# untitled.net
KiCad netlist of a schematic drawn in EAGLE
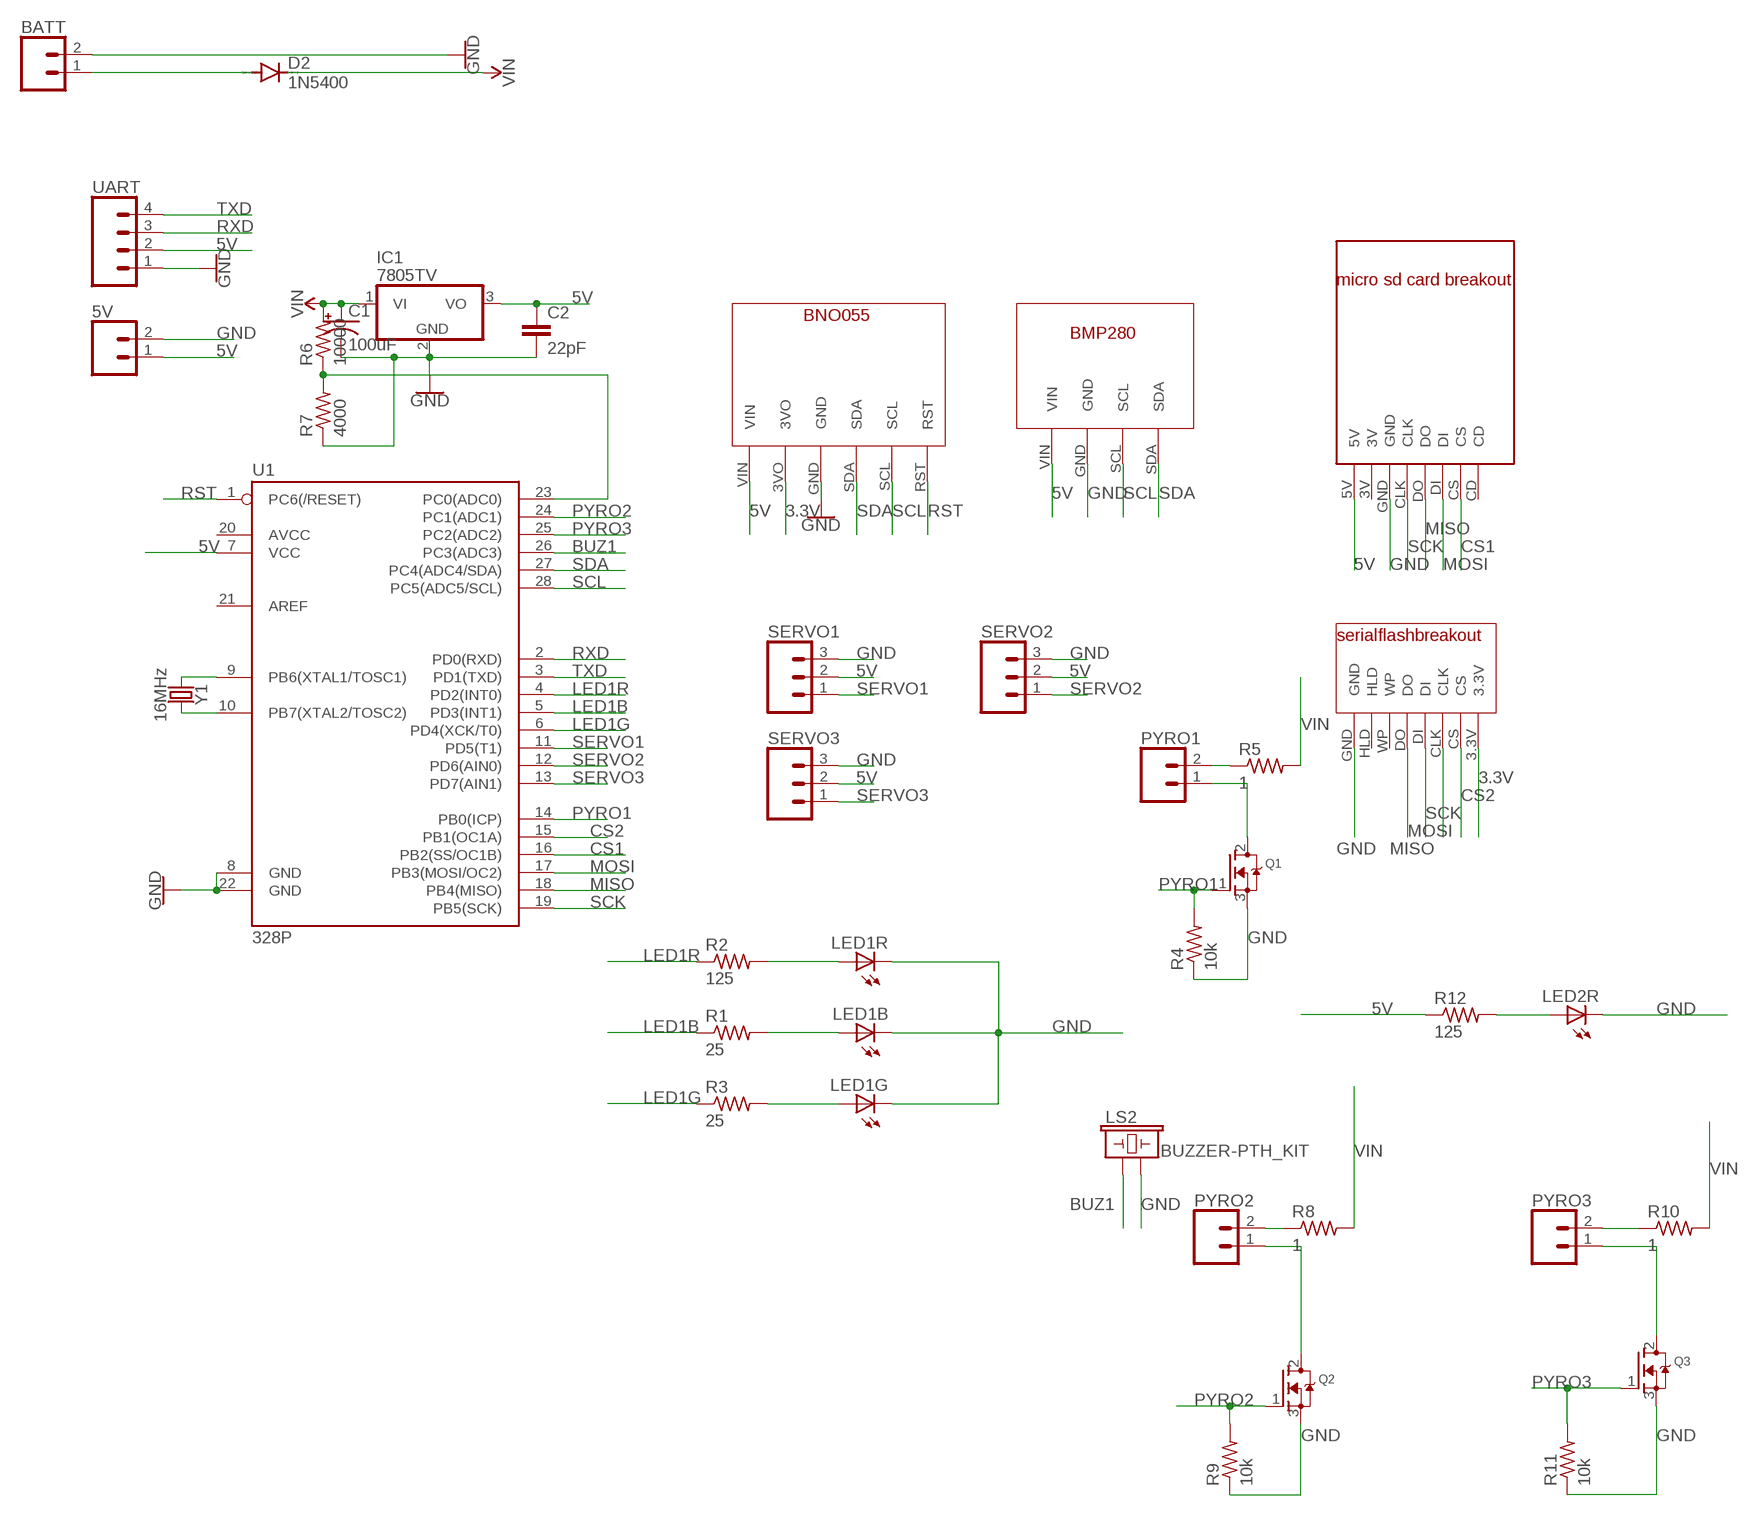
[diagram p0: schematic, sheet 1]

(export (version "E")
  (design (tool "Eeschema 10.0.6"))
  (components
    (comp (ref "5V")
      (value "CONN_02")
      (footprint "eagle-import:1X02")
      (libsource (lib "eagle-import") (part "CONN_02"))
    )
    (comp (ref "BATT")
      (value "CONN_02")
      (footprint "eagle-import:1X02")
      (libsource (lib "eagle-import") (part "CONN_02"))
    )
    (comp (ref "C1")
      (value "100uF")
      (footprint "eagle-import:CPOL-RADIAL-2.5MM-6.5MM")
      (libsource (lib "eagle-import") (part "100UF-POLAR-RADIAL-2.5MM-25V-20%"))
    )
    (comp (ref "C2")
      (value "22pF")
      (footprint "eagle-import:CAP-PTH-2.54")
      (libsource (lib "eagle-import") (part "22PF-PTH-2.54MM-200V-5%"))
    )
    (comp (ref "D2")
      (value "1N5400")
      (footprint "eagle-import:DO201-15")
      (libsource (lib "eagle-import") (part "1N5400"))
    )
    (comp (ref "IC1")
      (value "7805TV")
      (footprint "eagle-import:TO220V")
      (libsource (lib "eagle-import") (part "78TV05"))
    )
    (comp (ref "LED1B")
      (value "LED1B")
      (footprint "eagle-import:LED5MM")
      (libsource (lib "eagle-import") (part "LED5MM"))
    )
    (comp (ref "LED1G")
      (value "LED1G")
      (footprint "eagle-import:LED5MM")
      (libsource (lib "eagle-import") (part "LED5MM"))
    )
    (comp (ref "LED1R")
      (value "LED1R")
      (footprint "eagle-import:LED5MM")
      (libsource (lib "eagle-import") (part "LED5MM"))
    )
    (comp (ref "LED2R")
      (value "LED1R")
      (footprint "eagle-import:LED5MM")
      (libsource (lib "eagle-import") (part "LED5MM"))
    )
    (comp (ref "LS2")
      (value "BUZZER-PTH_KIT")
      (footprint "eagle-import:BUZZER-12MM-KIT")
      (libsource (lib "eagle-import") (part "BUZZER-PTH_KIT"))
    )
    (comp (ref "PYRO1")
      (value "CONN_02")
      (footprint "eagle-import:1X02")
      (libsource (lib "eagle-import") (part "SparkFun-Connectors_513_CONN_02"))
    )
    (comp (ref "PYRO2")
      (value "CONN_02")
      (footprint "eagle-import:1X02")
      (libsource (lib "eagle-import") (part "SparkFun-Connectors_513_CONN_02"))
    )
    (comp (ref "PYRO3")
      (value "CONN_02")
      (footprint "eagle-import:1X02")
      (libsource (lib "eagle-import") (part "SparkFun-Connectors_513_CONN_02"))
    )
    (comp (ref "Q1")
      (value "MOSFET-NGDS_TO220V")
      (footprint "eagle-import:TO220V")
      (libsource (lib "eagle-import") (part "MOSFET-NGDS_TO220V"))
    )
    (comp (ref "Q2")
      (value "MOSFET-NGDS_TO220V")
      (footprint "eagle-import:TO220V")
      (libsource (lib "eagle-import") (part "MOSFET-NGDS_TO220V"))
    )
    (comp (ref "Q3")
      (value "MOSFET-NGDS_TO220V")
      (footprint "eagle-import:TO220V")
      (libsource (lib "eagle-import") (part "MOSFET-NGDS_TO220V"))
    )
    (comp (ref "R1")
      (value "25")
      (footprint "eagle-import:0805-THM")
      (libsource (lib "eagle-import") (part "FLIPFLOP-RES"))
    )
    (comp (ref "R2")
      (value "125")
      (footprint "eagle-import:0805-THM")
      (libsource (lib "eagle-import") (part "FLIPFLOP-RES"))
    )
    (comp (ref "R3")
      (value "25")
      (footprint "eagle-import:0805-THM")
      (libsource (lib "eagle-import") (part "FLIPFLOP-RES"))
    )
    (comp (ref "R4")
      (value "10k")
      (footprint "eagle-import:0805-THM")
      (libsource (lib "eagle-import") (part "FLIPFLOP-RES"))
    )
    (comp (ref "R5")
      (value "1")
      (footprint "eagle-import:0805-THM")
      (libsource (lib "eagle-import") (part "FLIPFLOP-RES"))
    )
    (comp (ref "R6")
      (value "10000")
      (footprint "eagle-import:0805-THM")
      (libsource (lib "eagle-import") (part "FLIPFLOP-RES"))
    )
    (comp (ref "R7")
      (value "4000")
      (footprint "eagle-import:0805-THM")
      (libsource (lib "eagle-import") (part "FLIPFLOP-RES"))
    )
    (comp (ref "R8")
      (value "1")
      (footprint "eagle-import:0805-THM")
      (libsource (lib "eagle-import") (part "FLIPFLOP-RES"))
    )
    (comp (ref "R9")
      (value "10k")
      (footprint "eagle-import:0805-THM")
      (libsource (lib "eagle-import") (part "FLIPFLOP-RES"))
    )
    (comp (ref "R10")
      (value "1")
      (footprint "eagle-import:0805-THM")
      (libsource (lib "eagle-import") (part "FLIPFLOP-RES"))
    )
    (comp (ref "R11")
      (value "10k")
      (footprint "eagle-import:0805-THM")
      (libsource (lib "eagle-import") (part "FLIPFLOP-RES"))
    )
    (comp (ref "R12")
      (value "125")
      (footprint "eagle-import:0805-THM")
      (libsource (lib "eagle-import") (part "FLIPFLOP-RES"))
    )
    (comp (ref "SERVO1")
      (value "CONN_03")
      (footprint "eagle-import:1X03")
      (libsource (lib "eagle-import") (part "CONN_03"))
    )
    (comp (ref "SERVO2")
      (value "CONN_03")
      (footprint "eagle-import:1X03")
      (libsource (lib "eagle-import") (part "CONN_03"))
    )
    (comp (ref "SERVO3")
      (value "CONN_03")
      (footprint "eagle-import:1X03")
      (libsource (lib "eagle-import") (part "CONN_03"))
    )
    (comp (ref "U$1")
      (value "BNO055")
      (footprint "eagle-import:BNO055")
      (libsource (lib "eagle-import") (part "BNO055"))
    )
    (comp (ref "U$2")
      (value "BMP280")
      (footprint "eagle-import:BMP280")
      (libsource (lib "eagle-import") (part "BMP280"))
    )
    (comp (ref "U$3")
      (value "ADAFRUITSDCARD")
      (footprint "eagle-import:ADAFRUITSDCARD")
      (libsource (lib "eagle-import") (part "ADAFRUITSDCARD"))
    )
    (comp (ref "U$4")
      (value "SPARKFUNFLASHBREAKOUT")
      (footprint "eagle-import:SPARKFUNFLASHBREAKOUT")
      (libsource (lib "eagle-import") (part "SPARKFUNFLASHBREAKOUT"))
    )
    (comp (ref "U1")
      (value "328P")
      (footprint "eagle-import:DIP28")
      (libsource (lib "eagle-import") (part "ATMEGA328P_PDIP"))
    )
    (comp (ref "UART")
      (value "CONN_04PTH")
      (footprint "eagle-import:1X04")
      (libsource (lib "eagle-import") (part "CONN_04PTH"))
    )
    (comp (ref "Y1")
      (value "16MHz")
      (footprint "eagle-import:HC49US")
      (libsource (lib "eagle-import") (part "CRYSTAL-16MHZPTH-HC49US"))
    )
  )
  (nets
    (net (code "1") (name "/3.3V") (class "Default")
      (node (ref "U$1") (pin "3VO") (pinfunction "3VO_3VO") (pintype "bidirectional"))
      (node (ref "U$4") (pin "3.3V") (pinfunction "3.3V_3.3V") (pintype "bidirectional"))
    )
    (net (code "2") (name "/5V") (class "Default")
      (node (ref "5V") (pin "1") (pinfunction "1_1") (pintype "passive"))
      (node (ref "C2") (pin "1") (pinfunction "1_1") (pintype "passive"))
      (node (ref "IC1") (pin "3") (pinfunction "VO_3") (pintype "passive"))
      (node (ref "R12") (pin "1") (pinfunction "1_1") (pintype "passive"))
      (node (ref "SERVO1") (pin "2") (pinfunction "2_2") (pintype "passive"))
      (node (ref "SERVO2") (pin "2") (pinfunction "2_2") (pintype "passive"))
      (node (ref "SERVO3") (pin "2") (pinfunction "2_2") (pintype "passive"))
      (node (ref "U$1") (pin "VIN") (pinfunction "VIN_VIN") (pintype "bidirectional"))
      (node (ref "U$2") (pin "VIN") (pinfunction "VIN_VIN") (pintype "bidirectional"))
      (node (ref "U$3") (pin "5V") (pinfunction "5V_5V") (pintype "bidirectional"))
      (node (ref "U1") (pin "7") (pinfunction "VCC_7") (pintype "bidirectional"))
      (node (ref "UART") (pin "2") (pinfunction "2_2") (pintype "passive"))
    )
    (net (code "3") (name "/BUZ1") (class "Default")
      (node (ref "LS2") (pin "+") (pinfunction "1_+") (pintype "passive"))
      (node (ref "U1") (pin "26") (pinfunction "PC3(ADC3)_26") (pintype "bidirectional"))
    )
    (net (code "4") (name "/CS1") (class "Default")
      (node (ref "U$3") (pin "CS") (pinfunction "CS_CS") (pintype "bidirectional"))
      (node (ref "U1") (pin "16") (pinfunction "PB2(SS/OC1B)_16") (pintype "bidirectional"))
    )
    (net (code "5") (name "/CS2") (class "Default")
      (node (ref "U$4") (pin "CS") (pinfunction "CS_CS") (pintype "bidirectional"))
      (node (ref "U1") (pin "15") (pinfunction "PB1(OC1A)_15") (pintype "bidirectional"))
    )
    (net (code "6") (name "/LED1B") (class "Default")
      (node (ref "R1") (pin "1") (pinfunction "1_1") (pintype "passive"))
      (node (ref "U1") (pin "5") (pinfunction "PD3(INT1)_5") (pintype "bidirectional"))
    )
    (net (code "7") (name "/LED1G") (class "Default")
      (node (ref "R3") (pin "1") (pinfunction "1_1") (pintype "passive"))
      (node (ref "U1") (pin "6") (pinfunction "PD4(XCK/T0)_6") (pintype "bidirectional"))
    )
    (net (code "8") (name "/LED1R") (class "Default")
      (node (ref "R2") (pin "1") (pinfunction "1_1") (pintype "passive"))
      (node (ref "U1") (pin "4") (pinfunction "PD2(INT0)_4") (pintype "bidirectional"))
    )
    (net (code "9") (name "/MISO") (class "Default")
      (node (ref "U$3") (pin "DO") (pinfunction "DO_DO") (pintype "bidirectional"))
      (node (ref "U$4") (pin "DO") (pinfunction "DO_DO") (pintype "bidirectional"))
      (node (ref "U1") (pin "18") (pinfunction "PB4(MISO)_18") (pintype "bidirectional"))
    )
    (net (code "10") (name "/MOSI") (class "Default")
      (node (ref "U$3") (pin "DI") (pinfunction "DI_DI") (pintype "bidirectional"))
      (node (ref "U$4") (pin "DI") (pinfunction "DI_DI") (pintype "bidirectional"))
      (node (ref "U1") (pin "17") (pinfunction "PB3(MOSI/OC2)_17") (pintype "bidirectional"))
    )
    (net (code "11") (name "/PYRO1") (class "Default")
      (node (ref "Q1") (pin "1") (pinfunction "G_1") (pintype "bidirectional"))
      (node (ref "R4") (pin "2") (pinfunction "2_2") (pintype "passive"))
      (node (ref "U1") (pin "14") (pinfunction "PB0(ICP)_14") (pintype "bidirectional"))
    )
    (net (code "12") (name "/PYRO2") (class "Default")
      (node (ref "Q2") (pin "1") (pinfunction "G_1") (pintype "bidirectional"))
      (node (ref "R9") (pin "2") (pinfunction "2_2") (pintype "passive"))
      (node (ref "U1") (pin "24") (pinfunction "PC1(ADC1)_24") (pintype "bidirectional"))
    )
    (net (code "13") (name "/PYRO3") (class "Default")
      (node (ref "Q3") (pin "1") (pinfunction "G_1") (pintype "bidirectional"))
      (node (ref "R11") (pin "2") (pinfunction "2_2") (pintype "passive"))
      (node (ref "U1") (pin "25") (pinfunction "PC2(ADC2)_25") (pintype "bidirectional"))
    )
    (net (code "14") (name "/RST") (class "Default")
      (node (ref "U$1") (pin "RST") (pinfunction "RST_RST") (pintype "bidirectional"))
      (node (ref "U1") (pin "1") (pinfunction "PC6(/RESET)_1") (pintype "bidirectional"))
    )
    (net (code "15") (name "/RXD") (class "Default")
      (node (ref "U1") (pin "2") (pinfunction "PD0(RXD)_2") (pintype "bidirectional"))
      (node (ref "UART") (pin "3") (pinfunction "3_3") (pintype "passive"))
    )
    (net (code "16") (name "/SCK") (class "Default")
      (node (ref "U$3") (pin "CLK") (pinfunction "CLK_CLK") (pintype "bidirectional"))
      (node (ref "U$4") (pin "CLK") (pinfunction "CLK_CLK") (pintype "bidirectional"))
      (node (ref "U1") (pin "19") (pinfunction "PB5(SCK)_19") (pintype "bidirectional"))
    )
    (net (code "17") (name "/SCL") (class "Default")
      (node (ref "U$1") (pin "SCL") (pinfunction "SCL_SCL") (pintype "bidirectional"))
      (node (ref "U$2") (pin "SCL") (pinfunction "SCL_SCL") (pintype "bidirectional"))
      (node (ref "U1") (pin "28") (pinfunction "PC5(ADC5/SCL)_28") (pintype "bidirectional"))
    )
    (net (code "18") (name "/SDA") (class "Default")
      (node (ref "U$1") (pin "SDA") (pinfunction "SDA_SDA") (pintype "bidirectional"))
      (node (ref "U$2") (pin "SDA") (pinfunction "SDA_SDA") (pintype "bidirectional"))
      (node (ref "U1") (pin "27") (pinfunction "PC4(ADC4/SDA)_27") (pintype "bidirectional"))
    )
    (net (code "19") (name "/SERVO1") (class "Default")
      (node (ref "SERVO1") (pin "1") (pinfunction "1_1") (pintype "passive"))
      (node (ref "U1") (pin "11") (pinfunction "PD5(T1)_11") (pintype "bidirectional"))
    )
    (net (code "20") (name "/SERVO2") (class "Default")
      (node (ref "SERVO2") (pin "1") (pinfunction "1_1") (pintype "passive"))
      (node (ref "U1") (pin "12") (pinfunction "PD6(AIN0)_12") (pintype "bidirectional"))
    )
    (net (code "21") (name "/SERVO3") (class "Default")
      (node (ref "SERVO3") (pin "1") (pinfunction "1_1") (pintype "passive"))
      (node (ref "U1") (pin "13") (pinfunction "PD7(AIN1)_13") (pintype "bidirectional"))
    )
    (net (code "22") (name "/TXD") (class "Default")
      (node (ref "U1") (pin "3") (pinfunction "PD1(TXD)_3") (pintype "bidirectional"))
      (node (ref "UART") (pin "4") (pinfunction "4_4") (pintype "passive"))
    )
    (net (code "23") (name "GND") (class "Default")
      (node (ref "5V") (pin "2") (pinfunction "2_2") (pintype "passive"))
      (node (ref "BATT") (pin "2") (pinfunction "2_2") (pintype "passive"))
      (node (ref "C1") (pin "2") (pinfunction "-_2") (pintype "passive"))
      (node (ref "C2") (pin "2") (pinfunction "2_2") (pintype "passive"))
      (node (ref "IC1") (pin "2") (pinfunction "GND_2") (pintype "passive"))
      (node (ref "LED1B") (pin "K") (pinfunction "C_K") (pintype "passive"))
      (node (ref "LED1G") (pin "K") (pinfunction "C_K") (pintype "passive"))
      (node (ref "LED1R") (pin "K") (pinfunction "C_K") (pintype "passive"))
      (node (ref "LED2R") (pin "K") (pinfunction "C_K") (pintype "passive"))
      (node (ref "LS2") (pin "-") (pinfunction "2_-") (pintype "passive"))
      (node (ref "Q1") (pin "3") (pinfunction "S_3") (pintype "bidirectional"))
      (node (ref "Q2") (pin "3") (pinfunction "S_3") (pintype "bidirectional"))
      (node (ref "Q3") (pin "3") (pinfunction "S_3") (pintype "bidirectional"))
      (node (ref "R11") (pin "1") (pinfunction "1_1") (pintype "passive"))
      (node (ref "R4") (pin "1") (pinfunction "1_1") (pintype "passive"))
      (node (ref "R7") (pin "1") (pinfunction "1_1") (pintype "passive"))
      (node (ref "R9") (pin "1") (pinfunction "1_1") (pintype "passive"))
      (node (ref "SERVO1") (pin "3") (pinfunction "3_3") (pintype "passive"))
      (node (ref "SERVO2") (pin "3") (pinfunction "3_3") (pintype "passive"))
      (node (ref "SERVO3") (pin "3") (pinfunction "3_3") (pintype "passive"))
      (node (ref "U$1") (pin "GND") (pinfunction "GND_GND") (pintype "bidirectional"))
      (node (ref "U$2") (pin "GND") (pinfunction "GND_GND") (pintype "bidirectional"))
      (node (ref "U$3") (pin "GND") (pinfunction "GND_GND") (pintype "bidirectional"))
      (node (ref "U$4") (pin "GND") (pinfunction "GND_GND") (pintype "bidirectional"))
      (node (ref "U1") (pin "22") (pinfunction "GND_22") (pintype "bidirectional"))
      (node (ref "U1") (pin "8") (pinfunction "GND_8") (pintype "bidirectional"))
      (node (ref "UART") (pin "1") (pinfunction "1_1") (pintype "passive"))
    )
    (net (code "24") (name "Net-(BATT-Pad1)") (class "Default")
      (node (ref "BATT") (pin "1") (pinfunction "1_1") (pintype "passive"))
      (node (ref "D2") (pin "A") (pinfunction "A_A") (pintype "passive"))
    )
    (net (code "25") (name "Net-(LED1B-PadA)") (class "Default")
      (node (ref "LED1B") (pin "A") (pinfunction "A_A") (pintype "passive"))
      (node (ref "R1") (pin "2") (pinfunction "2_2") (pintype "passive"))
    )
    (net (code "26") (name "Net-(LED1G-PadA)") (class "Default")
      (node (ref "LED1G") (pin "A") (pinfunction "A_A") (pintype "passive"))
      (node (ref "R3") (pin "2") (pinfunction "2_2") (pintype "passive"))
    )
    (net (code "27") (name "Net-(LED1R-PadA)") (class "Default")
      (node (ref "LED1R") (pin "A") (pinfunction "A_A") (pintype "passive"))
      (node (ref "R2") (pin "2") (pinfunction "2_2") (pintype "passive"))
    )
    (net (code "28") (name "Net-(LED2R-PadA)") (class "Default")
      (node (ref "LED2R") (pin "A") (pinfunction "A_A") (pintype "passive"))
      (node (ref "R12") (pin "2") (pinfunction "2_2") (pintype "passive"))
    )
    (net (code "29") (name "Net-(PYRO1-Pad2)") (class "Default")
      (node (ref "PYRO1") (pin "2") (pinfunction "2_2") (pintype "passive"))
      (node (ref "R5") (pin "1") (pinfunction "1_1") (pintype "passive"))
    )
    (net (code "30") (name "Net-(PYRO2-Pad2)") (class "Default")
      (node (ref "PYRO2") (pin "2") (pinfunction "2_2") (pintype "passive"))
      (node (ref "R8") (pin "1") (pinfunction "1_1") (pintype "passive"))
    )
    (net (code "31") (name "Net-(PYRO3-Pad2)") (class "Default")
      (node (ref "PYRO3") (pin "2") (pinfunction "2_2") (pintype "passive"))
      (node (ref "R10") (pin "1") (pinfunction "1_1") (pintype "passive"))
    )
    (net (code "32") (name "Net-(Q1-D)") (class "Default")
      (node (ref "PYRO1") (pin "1") (pinfunction "1_1") (pintype "passive"))
      (node (ref "Q1") (pin "2") (pinfunction "D_2") (pintype "bidirectional"))
    )
    (net (code "33") (name "Net-(Q2-D)") (class "Default")
      (node (ref "PYRO2") (pin "1") (pinfunction "1_1") (pintype "passive"))
      (node (ref "Q2") (pin "2") (pinfunction "D_2") (pintype "bidirectional"))
    )
    (net (code "34") (name "Net-(Q3-D)") (class "Default")
      (node (ref "PYRO3") (pin "1") (pinfunction "1_1") (pintype "passive"))
      (node (ref "Q3") (pin "2") (pinfunction "D_2") (pintype "bidirectional"))
    )
    (net (code "35") (name "Net-(U1-PB6(XTAL1{slash}TOSC1))") (class "Default")
      (node (ref "U1") (pin "9") (pinfunction "PB6(XTAL1/TOSC1)_9") (pintype "bidirectional"))
      (node (ref "Y1") (pin "1") (pinfunction "1_1") (pintype "passive"))
    )
    (net (code "36") (name "Net-(U1-PB7(XTAL2{slash}TOSC2))") (class "Default")
      (node (ref "U1") (pin "10") (pinfunction "PB7(XTAL2/TOSC2)_10") (pintype "bidirectional"))
      (node (ref "Y1") (pin "2") (pinfunction "2_2") (pintype "passive"))
    )
    (net (code "37") (name "Net-(U1-PC0(ADC0))") (class "Default")
      (node (ref "R6") (pin "1") (pinfunction "1_1") (pintype "passive"))
      (node (ref "R7") (pin "2") (pinfunction "2_2") (pintype "passive"))
      (node (ref "U1") (pin "23") (pinfunction "PC0(ADC0)_23") (pintype "bidirectional"))
    )
    (net (code "38") (name "VIN") (class "Default")
      (node (ref "C1") (pin "1") (pinfunction "+_1") (pintype "passive"))
      (node (ref "D2") (pin "C") (pinfunction "C_C") (pintype "passive"))
      (node (ref "IC1") (pin "1") (pinfunction "VI_1") (pintype "input"))
      (node (ref "R10") (pin "2") (pinfunction "2_2") (pintype "passive"))
      (node (ref "R5") (pin "2") (pinfunction "2_2") (pintype "passive"))
      (node (ref "R6") (pin "2") (pinfunction "2_2") (pintype "passive"))
      (node (ref "R8") (pin "2") (pinfunction "2_2") (pintype "passive"))
    )
    (net (code "39") (name "unconnected-(U$3-Pad3V)") (class "Default")
      (node (ref "U$3") (pin "3V") (pinfunction "3V_3V") (pintype "bidirectional"))
    )
    (net (code "40") (name "unconnected-(U$3-PadCD)") (class "Default")
      (node (ref "U$3") (pin "CD") (pinfunction "CD_CD") (pintype "bidirectional"))
    )
    (net (code "41") (name "unconnected-(U$4-PadHLD)") (class "Default")
      (node (ref "U$4") (pin "HLD") (pinfunction "HLD_HLD") (pintype "bidirectional"))
    )
    (net (code "42") (name "unconnected-(U$4-PadWP)") (class "Default")
      (node (ref "U$4") (pin "WP") (pinfunction "WP_WP") (pintype "bidirectional"))
    )
    (net (code "43") (name "unconnected-(U1-AREF-Pad21)") (class "Default")
      (node (ref "U1") (pin "21") (pinfunction "AREF_21") (pintype "bidirectional"))
    )
    (net (code "44") (name "unconnected-(U1-AVCC-Pad20)") (class "Default")
      (node (ref "U1") (pin "20") (pinfunction "AVCC_20") (pintype "bidirectional"))
    )
  )
)
